# uDJV_board_1_v1_1.net
KiCad netlist of a schematic drawn in EAGLE
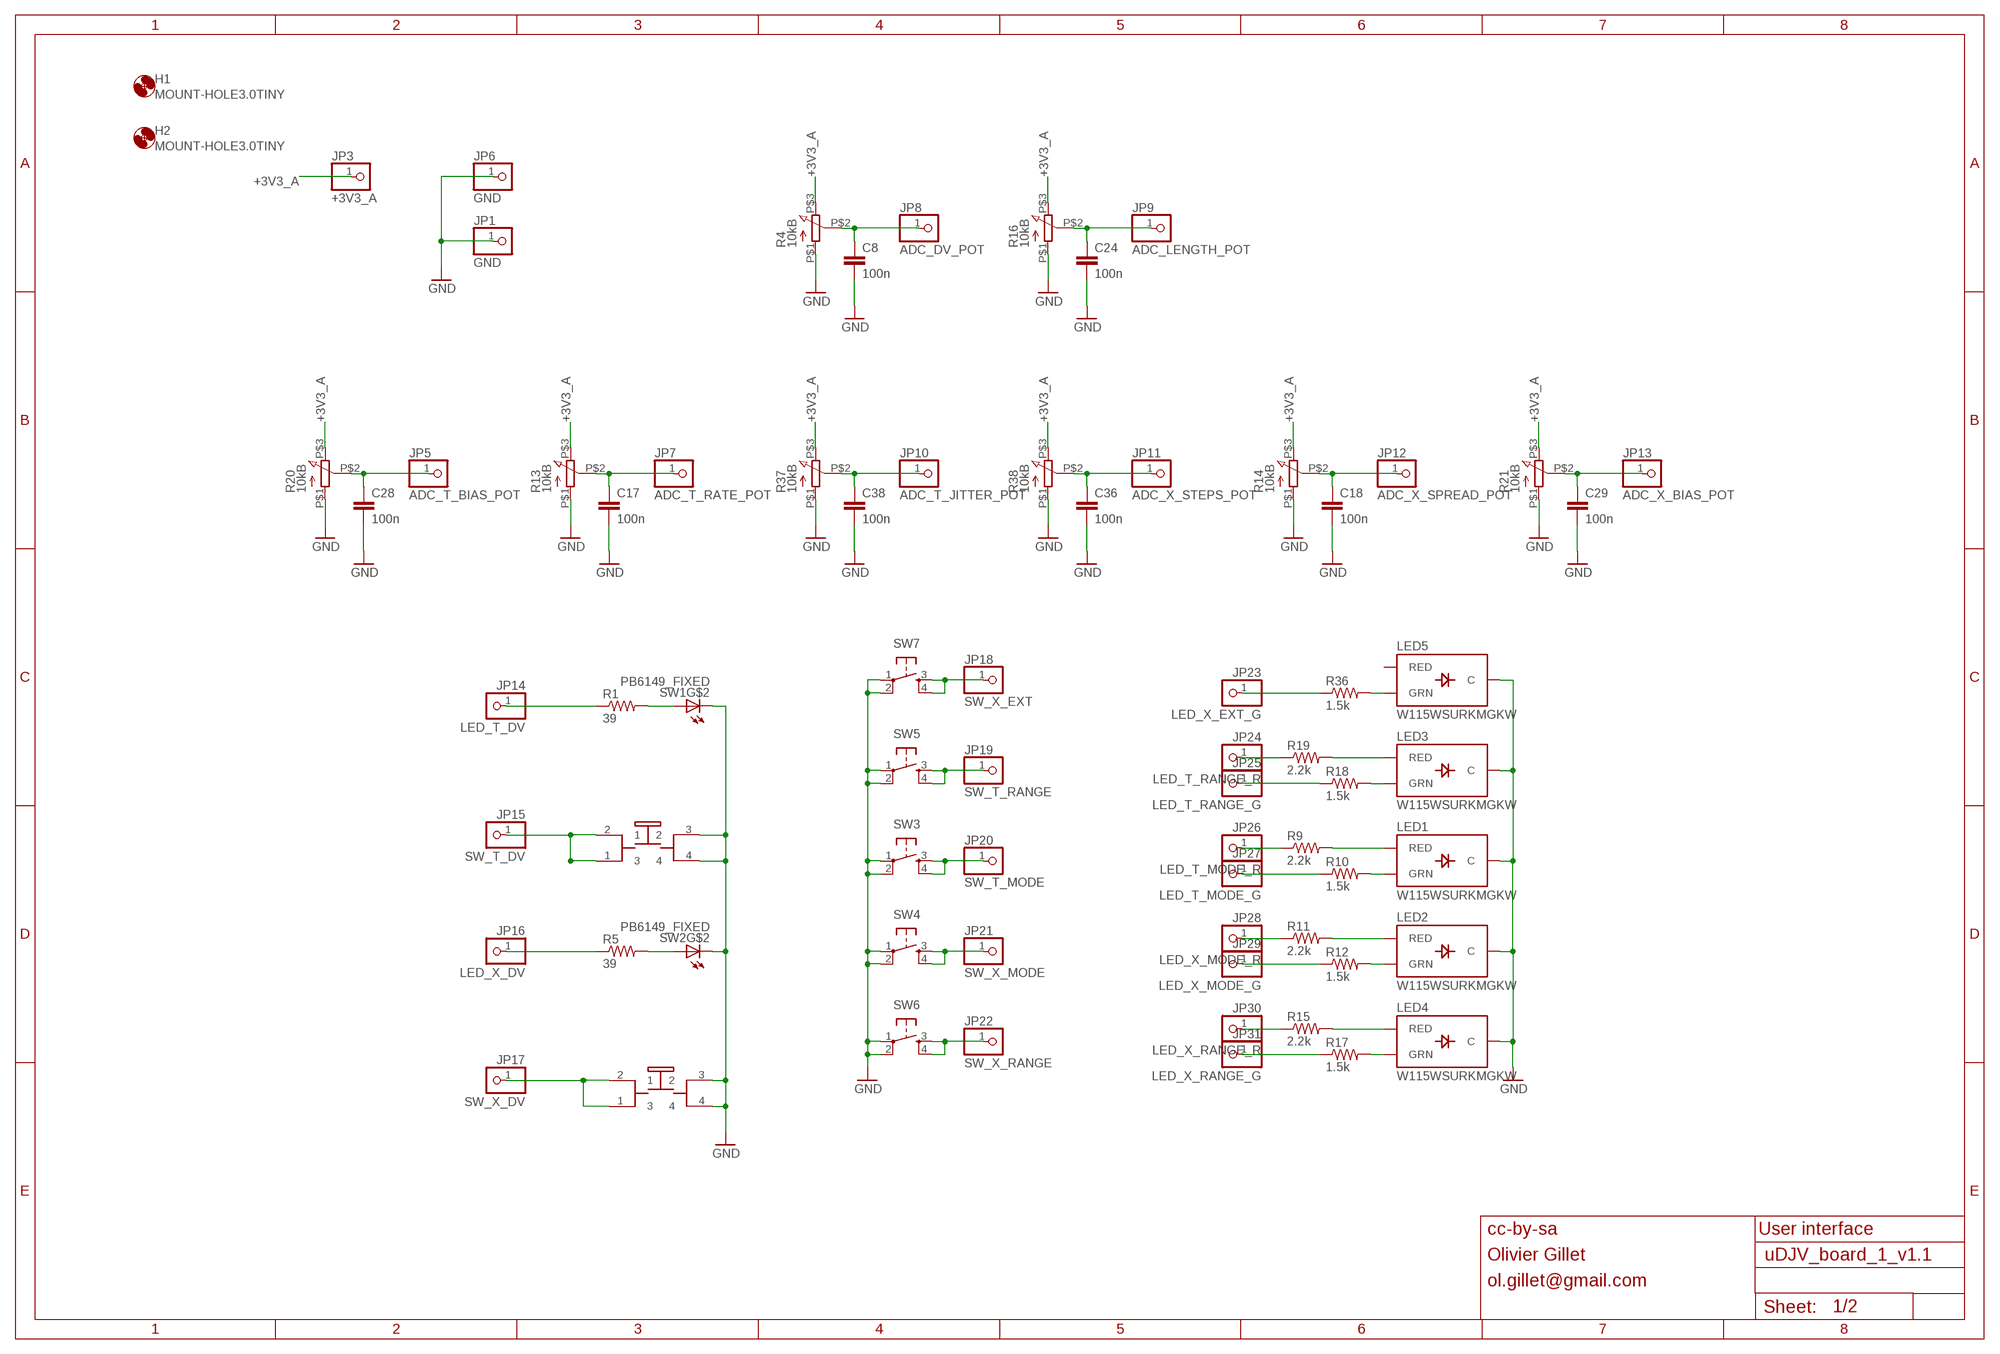
[diagram p0: schematic, sheet 1]
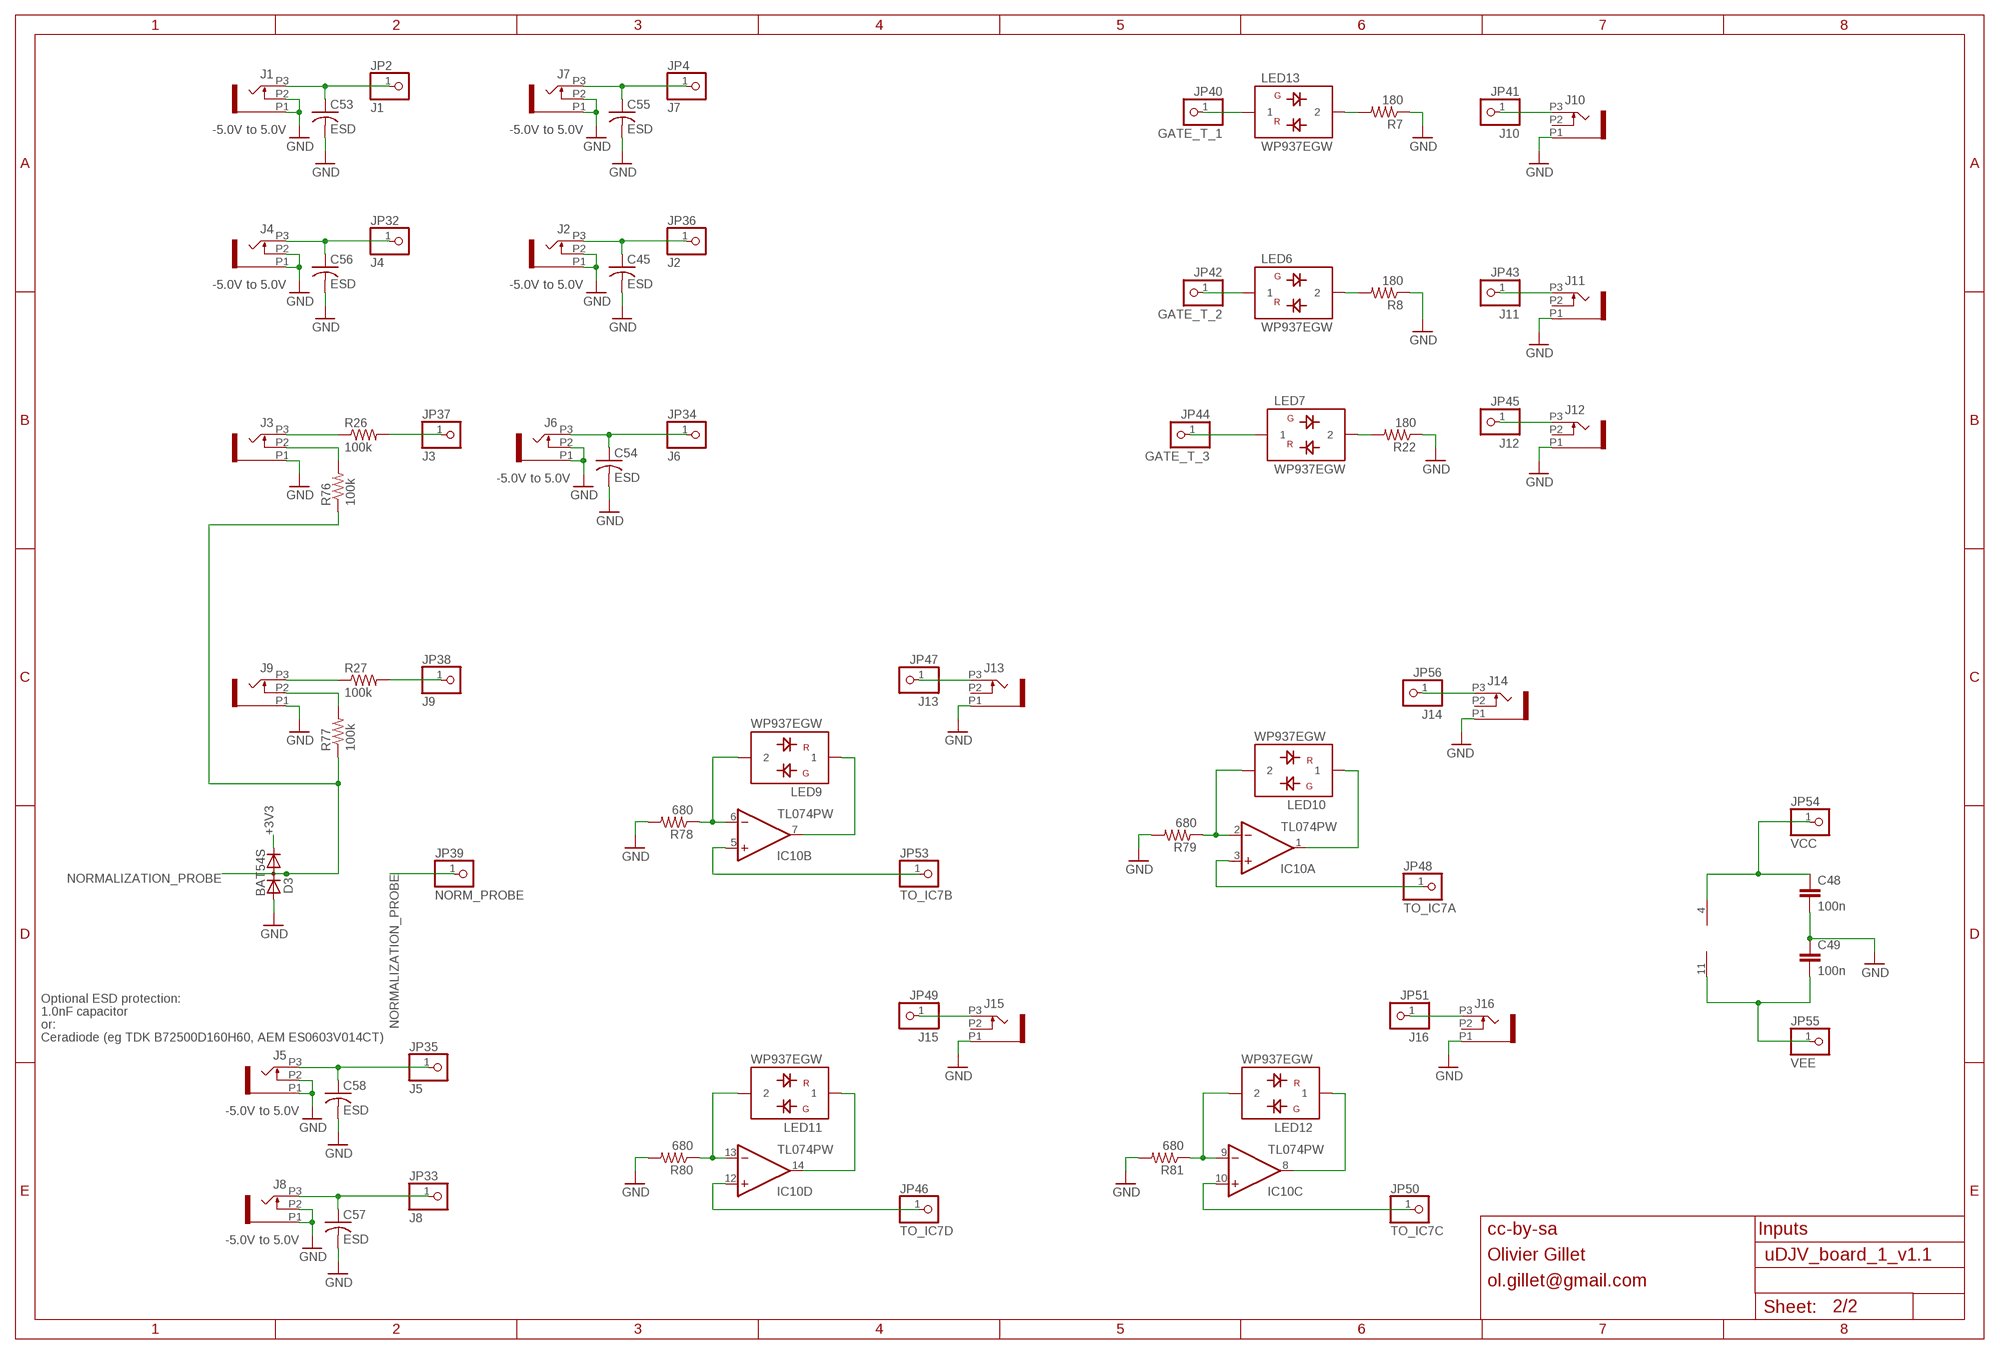
[diagram p1: schematic, sheet 2]

(export (version "E")
  (design (tool "Eeschema 10.0.6"))
  (components
    (comp (ref "C45")
      (value "ESD")
      (footprint "eagle-import:C0603")
      (libsource (lib "eagle-import") (part "C-USC0603"))
    )
    (comp (ref "C48")
      (value "100n")
      (footprint "eagle-import:PARTS_AMAN_RESISTOR_0603")
      (libsource (lib "eagle-import") (part "PARTS_AMAN_CAPACITOR"))
    )
    (comp (ref "C49")
      (value "100n")
      (footprint "eagle-import:PARTS_AMAN_RESISTOR_0603")
      (libsource (lib "eagle-import") (part "PARTS_AMAN_CAPACITOR"))
    )
    (comp (ref "C53")
      (value "ESD")
      (footprint "eagle-import:C0603")
      (libsource (lib "eagle-import") (part "C-USC0603"))
    )
    (comp (ref "C54")
      (value "ESD")
      (footprint "eagle-import:C0603")
      (libsource (lib "eagle-import") (part "C-USC0603"))
    )
    (comp (ref "C55")
      (value "ESD")
      (footprint "eagle-import:C0603")
      (libsource (lib "eagle-import") (part "C-USC0603"))
    )
    (comp (ref "C56")
      (value "ESD")
      (footprint "eagle-import:C0603")
      (libsource (lib "eagle-import") (part "C-USC0603"))
    )
    (comp (ref "C57")
      (value "ESD")
      (footprint "eagle-import:C0603")
      (libsource (lib "eagle-import") (part "C-USC0603"))
    )
    (comp (ref "C58")
      (value "ESD")
      (footprint "eagle-import:C0603")
      (libsource (lib "eagle-import") (part "C-USC0603"))
    )
    (comp (ref "D3")
      (value "BAT54S")
      (footprint "eagle-import:SOT23")
      (libsource (lib "eagle-import") (part "DIODE_2CACA-SOT23"))
    )
    (comp (ref "IC10")
      (value "TL074PW")
      (footprint "eagle-import:TSSOP14_065")
      (libsource (lib "eagle-import") (part "TL074PW"))
    )
    (comp (ref "J1")
      (value "PJ301_THONKICONN6")
      (footprint "eagle-import:WQP_PJ_301M6")
      (libsource (lib "eagle-import") (part "PJ301_THONKICONN6"))
    )
    (comp (ref "J2")
      (value "PJ301_THONKICONN6")
      (footprint "eagle-import:WQP_PJ_301M6")
      (libsource (lib "eagle-import") (part "PJ301_THONKICONN6"))
    )
    (comp (ref "J3")
      (value "PJ301_THONKICONN6")
      (footprint "eagle-import:WQP_PJ_301M6")
      (libsource (lib "eagle-import") (part "PJ301_THONKICONN6"))
    )
    (comp (ref "J4")
      (value "PJ301_THONKICONN6")
      (footprint "eagle-import:WQP_PJ_301M6")
      (libsource (lib "eagle-import") (part "PJ301_THONKICONN6"))
    )
    (comp (ref "J5")
      (value "PJ301_THONKICONN6")
      (footprint "eagle-import:WQP_PJ_301M6")
      (libsource (lib "eagle-import") (part "PJ301_THONKICONN6"))
    )
    (comp (ref "J6")
      (value "PJ301_THONKICONN6")
      (footprint "eagle-import:WQP_PJ_301M6")
      (libsource (lib "eagle-import") (part "PJ301_THONKICONN6"))
    )
    (comp (ref "J7")
      (value "PJ301_THONKICONN6")
      (footprint "eagle-import:WQP_PJ_301M6")
      (libsource (lib "eagle-import") (part "PJ301_THONKICONN6"))
    )
    (comp (ref "J8")
      (value "PJ301_THONKICONN6")
      (footprint "eagle-import:WQP_PJ_301M6")
      (libsource (lib "eagle-import") (part "PJ301_THONKICONN6"))
    )
    (comp (ref "J9")
      (value "PJ301_THONKICONN6")
      (footprint "eagle-import:WQP_PJ_301M6")
      (libsource (lib "eagle-import") (part "PJ301_THONKICONN6"))
    )
    (comp (ref "J10")
      (value "PJ301_THONKICONN6")
      (footprint "eagle-import:WQP_PJ_301M6")
      (libsource (lib "eagle-import") (part "PJ301_THONKICONN6"))
    )
    (comp (ref "J11")
      (value "PJ301_THONKICONN6")
      (footprint "eagle-import:WQP_PJ_301M6")
      (libsource (lib "eagle-import") (part "PJ301_THONKICONN6"))
    )
    (comp (ref "J12")
      (value "PJ301_THONKICONN6")
      (footprint "eagle-import:WQP_PJ_301M6")
      (libsource (lib "eagle-import") (part "PJ301_THONKICONN6"))
    )
    (comp (ref "J13")
      (value "PJ301_THONKICONN6")
      (footprint "eagle-import:WQP_PJ_301M6")
      (libsource (lib "eagle-import") (part "PJ301_THONKICONN6"))
    )
    (comp (ref "J14")
      (value "PJ301_THONKICONN6")
      (footprint "eagle-import:WQP_PJ_301M6")
      (libsource (lib "eagle-import") (part "PJ301_THONKICONN6"))
    )
    (comp (ref "J15")
      (value "PJ301_THONKICONN6")
      (footprint "eagle-import:WQP_PJ_301M6")
      (libsource (lib "eagle-import") (part "PJ301_THONKICONN6"))
    )
    (comp (ref "J16")
      (value "PJ301_THONKICONN6")
      (footprint "eagle-import:WQP_PJ_301M6")
      (libsource (lib "eagle-import") (part "PJ301_THONKICONN6"))
    )
    (comp (ref "JP2")
      (value "J1")
      (footprint "eagle-import:PARTS_AMAN_1X01")
      (libsource (lib "eagle-import") (part "PARTS_AMAN_PINHD-1X1"))
    )
    (comp (ref "JP4")
      (value "J7")
      (footprint "eagle-import:PARTS_AMAN_1X01")
      (libsource (lib "eagle-import") (part "PARTS_AMAN_PINHD-1X1"))
    )
    (comp (ref "JP32")
      (value "J4")
      (footprint "eagle-import:PARTS_AMAN_1X01")
      (libsource (lib "eagle-import") (part "PARTS_AMAN_PINHD-1X1"))
    )
    (comp (ref "JP33")
      (value "J8")
      (footprint "eagle-import:PARTS_AMAN_1X01")
      (libsource (lib "eagle-import") (part "PARTS_AMAN_PINHD-1X1"))
    )
    (comp (ref "JP34")
      (value "J6")
      (footprint "eagle-import:PARTS_AMAN_1X01")
      (libsource (lib "eagle-import") (part "PARTS_AMAN_PINHD-1X1"))
    )
    (comp (ref "JP35")
      (value "J5")
      (footprint "eagle-import:PARTS_AMAN_1X01")
      (libsource (lib "eagle-import") (part "PARTS_AMAN_PINHD-1X1"))
    )
    (comp (ref "JP36")
      (value "J2")
      (footprint "eagle-import:PARTS_AMAN_1X01")
      (libsource (lib "eagle-import") (part "PARTS_AMAN_PINHD-1X1"))
    )
    (comp (ref "JP37")
      (value "J3")
      (footprint "eagle-import:PARTS_AMAN_1X01")
      (libsource (lib "eagle-import") (part "PARTS_AMAN_PINHD-1X1"))
    )
    (comp (ref "JP38")
      (value "J9")
      (footprint "eagle-import:PARTS_AMAN_1X01")
      (libsource (lib "eagle-import") (part "PARTS_AMAN_PINHD-1X1"))
    )
    (comp (ref "JP39")
      (value "NORM_PROBE")
      (footprint "eagle-import:PARTS_AMAN_1X01")
      (libsource (lib "eagle-import") (part "PARTS_AMAN_PINHD-1X1"))
    )
    (comp (ref "JP40")
      (value "GATE_T_1")
      (footprint "eagle-import:PARTS_AMAN_1X01")
      (libsource (lib "eagle-import") (part "PARTS_AMAN_PINHD-1X1"))
    )
    (comp (ref "JP41")
      (value "J10")
      (footprint "eagle-import:PARTS_AMAN_1X01")
      (libsource (lib "eagle-import") (part "PARTS_AMAN_PINHD-1X1"))
    )
    (comp (ref "JP42")
      (value "GATE_T_2")
      (footprint "eagle-import:PARTS_AMAN_1X01")
      (libsource (lib "eagle-import") (part "PARTS_AMAN_PINHD-1X1"))
    )
    (comp (ref "JP43")
      (value "J11")
      (footprint "eagle-import:PARTS_AMAN_1X01")
      (libsource (lib "eagle-import") (part "PARTS_AMAN_PINHD-1X1"))
    )
    (comp (ref "JP44")
      (value "GATE_T_3")
      (footprint "eagle-import:PARTS_AMAN_1X01")
      (libsource (lib "eagle-import") (part "PARTS_AMAN_PINHD-1X1"))
    )
    (comp (ref "JP45")
      (value "J12")
      (footprint "eagle-import:PARTS_AMAN_1X01")
      (libsource (lib "eagle-import") (part "PARTS_AMAN_PINHD-1X1"))
    )
    (comp (ref "JP46")
      (value "TO_IC7D")
      (footprint "eagle-import:PARTS_AMAN_1X01")
      (libsource (lib "eagle-import") (part "PARTS_AMAN_PINHD-1X1"))
    )
    (comp (ref "JP47")
      (value "J13")
      (footprint "eagle-import:PARTS_AMAN_1X01")
      (libsource (lib "eagle-import") (part "PARTS_AMAN_PINHD-1X1"))
    )
    (comp (ref "JP48")
      (value "TO_IC7A")
      (footprint "eagle-import:PARTS_AMAN_1X01")
      (libsource (lib "eagle-import") (part "PARTS_AMAN_PINHD-1X1"))
    )
    (comp (ref "JP49")
      (value "J15")
      (footprint "eagle-import:PARTS_AMAN_1X01")
      (libsource (lib "eagle-import") (part "PARTS_AMAN_PINHD-1X1"))
    )
    (comp (ref "JP50")
      (value "TO_IC7C")
      (footprint "eagle-import:PARTS_AMAN_1X01")
      (libsource (lib "eagle-import") (part "PARTS_AMAN_PINHD-1X1"))
    )
    (comp (ref "JP51")
      (value "J16")
      (footprint "eagle-import:PARTS_AMAN_1X01")
      (libsource (lib "eagle-import") (part "PARTS_AMAN_PINHD-1X1"))
    )
    (comp (ref "JP53")
      (value "TO_IC7B")
      (footprint "eagle-import:PARTS_AMAN_1X01")
      (libsource (lib "eagle-import") (part "PARTS_AMAN_PINHD-1X1"))
    )
    (comp (ref "JP54")
      (value "VCC")
      (footprint "eagle-import:PARTS_AMAN_1X01")
      (libsource (lib "eagle-import") (part "PARTS_AMAN_PINHD-1X1"))
    )
    (comp (ref "JP55")
      (value "VEE")
      (footprint "eagle-import:PARTS_AMAN_1X01")
      (libsource (lib "eagle-import") (part "PARTS_AMAN_PINHD-1X1"))
    )
    (comp (ref "JP56")
      (value "J14")
      (footprint "eagle-import:PARTS_AMAN_1X01")
      (libsource (lib "eagle-import") (part "PARTS_AMAN_PINHD-1X1"))
    )
    (comp (ref "LED6")
      (value "WP937EGW")
      (footprint "eagle-import:LED3MM")
      (libsource (lib "eagle-import") (part "LED-BICOLOR-SHARED-THROUGHHOLE"))
    )
    (comp (ref "LED7")
      (value "WP937EGW")
      (footprint "eagle-import:LED3MM")
      (libsource (lib "eagle-import") (part "LED-BICOLOR-SHARED-THROUGHHOLE"))
    )
    (comp (ref "LED9")
      (value "WP937EGW")
      (footprint "eagle-import:LED3MM")
      (libsource (lib "eagle-import") (part "LED-BICOLOR-SHARED-THROUGHHOLE"))
    )
    (comp (ref "LED10")
      (value "WP937EGW")
      (footprint "eagle-import:LED3MM")
      (libsource (lib "eagle-import") (part "LED-BICOLOR-SHARED-THROUGHHOLE"))
    )
    (comp (ref "LED11")
      (value "WP937EGW")
      (footprint "eagle-import:LED3MM")
      (libsource (lib "eagle-import") (part "LED-BICOLOR-SHARED-THROUGHHOLE"))
    )
    (comp (ref "LED12")
      (value "WP937EGW")
      (footprint "eagle-import:LED3MM")
      (libsource (lib "eagle-import") (part "LED-BICOLOR-SHARED-THROUGHHOLE"))
    )
    (comp (ref "LED13")
      (value "WP937EGW")
      (footprint "eagle-import:LED3MM")
      (libsource (lib "eagle-import") (part "LED-BICOLOR-SHARED-THROUGHHOLE"))
    )
    (comp (ref "R7")
      (value "180")
      (footprint "eagle-import:PARTS_AMAN_RESISTOR_0603")
      (libsource (lib "eagle-import") (part "PARTS_AMAN_RESISTOR"))
    )
    (comp (ref "R8")
      (value "180")
      (footprint "eagle-import:PARTS_AMAN_RESISTOR_0603")
      (libsource (lib "eagle-import") (part "PARTS_AMAN_RESISTOR"))
    )
    (comp (ref "R22")
      (value "180")
      (footprint "eagle-import:PARTS_AMAN_RESISTOR_0603")
      (libsource (lib "eagle-import") (part "PARTS_AMAN_RESISTOR"))
    )
    (comp (ref "R26")
      (value "100k")
      (footprint "eagle-import:PARTS_AMAN_RESISTOR_0603")
      (libsource (lib "eagle-import") (part "PARTS_AMAN_RESISTOR"))
    )
    (comp (ref "R27")
      (value "100k")
      (footprint "eagle-import:PARTS_AMAN_RESISTOR_0603")
      (libsource (lib "eagle-import") (part "PARTS_AMAN_RESISTOR"))
    )
    (comp (ref "R76")
      (value "100k")
      (footprint "eagle-import:PARTS_AMAN_RESISTOR_0603")
      (libsource (lib "eagle-import") (part "PARTS_AMAN_RESISTOR"))
    )
    (comp (ref "R77")
      (value "100k")
      (footprint "eagle-import:PARTS_AMAN_RESISTOR_0603")
      (libsource (lib "eagle-import") (part "PARTS_AMAN_RESISTOR"))
    )
    (comp (ref "R78")
      (value "680")
      (footprint "eagle-import:PARTS_AMAN_RESISTOR_0603")
      (libsource (lib "eagle-import") (part "PARTS_AMAN_RESISTOR"))
    )
    (comp (ref "R79")
      (value "680")
      (footprint "eagle-import:PARTS_AMAN_RESISTOR_0603")
      (libsource (lib "eagle-import") (part "PARTS_AMAN_RESISTOR"))
    )
    (comp (ref "R80")
      (value "680")
      (footprint "eagle-import:PARTS_AMAN_RESISTOR_0603")
      (libsource (lib "eagle-import") (part "PARTS_AMAN_RESISTOR"))
    )
    (comp (ref "R81")
      (value "680")
      (footprint "eagle-import:PARTS_AMAN_RESISTOR_0603")
      (libsource (lib "eagle-import") (part "PARTS_AMAN_RESISTOR"))
    )
    (comp (ref "C8")
      (value "100n")
      (footprint "eagle-import:PARTS_AMAN_RESISTOR_0603")
      (libsource (lib "eagle-import") (part "PARTS_AMAN_CAPACITOR"))
    )
    (comp (ref "C17")
      (value "100n")
      (footprint "eagle-import:PARTS_AMAN_RESISTOR_0603")
      (libsource (lib "eagle-import") (part "PARTS_AMAN_CAPACITOR"))
    )
    (comp (ref "C18")
      (value "100n")
      (footprint "eagle-import:PARTS_AMAN_RESISTOR_0603")
      (libsource (lib "eagle-import") (part "PARTS_AMAN_CAPACITOR"))
    )
    (comp (ref "C24")
      (value "100n")
      (footprint "eagle-import:PARTS_AMAN_RESISTOR_0603")
      (libsource (lib "eagle-import") (part "PARTS_AMAN_CAPACITOR"))
    )
    (comp (ref "C28")
      (value "100n")
      (footprint "eagle-import:PARTS_AMAN_RESISTOR_0603")
      (libsource (lib "eagle-import") (part "PARTS_AMAN_CAPACITOR"))
    )
    (comp (ref "C29")
      (value "100n")
      (footprint "eagle-import:PARTS_AMAN_RESISTOR_0603")
      (libsource (lib "eagle-import") (part "PARTS_AMAN_CAPACITOR"))
    )
    (comp (ref "C36")
      (value "100n")
      (footprint "eagle-import:PARTS_AMAN_RESISTOR_0603")
      (libsource (lib "eagle-import") (part "PARTS_AMAN_CAPACITOR"))
    )
    (comp (ref "C38")
      (value "100n")
      (footprint "eagle-import:PARTS_AMAN_RESISTOR_0603")
      (libsource (lib "eagle-import") (part "PARTS_AMAN_CAPACITOR"))
    )
    (comp (ref "H1")
      (value "MOUNT-HOLE3.0TINY")
      (footprint "eagle-import:3,0TINY")
      (libsource (lib "eagle-import") (part "MOUNT-HOLE3.0TINY"))
    )
    (comp (ref "H2")
      (value "MOUNT-HOLE3.0TINY")
      (footprint "eagle-import:3,0TINY")
      (libsource (lib "eagle-import") (part "MOUNT-HOLE3.0TINY"))
    )
    (comp (ref "JP1")
      (value "GND")
      (footprint "eagle-import:PARTS_AMAN_1X01")
      (libsource (lib "eagle-import") (part "PARTS_AMAN_PINHD-1X1"))
    )
    (comp (ref "JP3")
      (value "+3V3_A")
      (footprint "eagle-import:PARTS_AMAN_1X01")
      (libsource (lib "eagle-import") (part "PARTS_AMAN_PINHD-1X1"))
    )
    (comp (ref "JP5")
      (value "ADC_T_BIAS_POT")
      (footprint "eagle-import:PARTS_AMAN_1X01")
      (libsource (lib "eagle-import") (part "PARTS_AMAN_PINHD-1X1"))
    )
    (comp (ref "JP6")
      (value "GND")
      (footprint "eagle-import:PARTS_AMAN_1X01")
      (libsource (lib "eagle-import") (part "PARTS_AMAN_PINHD-1X1"))
    )
    (comp (ref "JP7")
      (value "ADC_T_RATE_POT")
      (footprint "eagle-import:PARTS_AMAN_1X01")
      (libsource (lib "eagle-import") (part "PARTS_AMAN_PINHD-1X1"))
    )
    (comp (ref "JP8")
      (value "ADC_DV_POT")
      (footprint "eagle-import:PARTS_AMAN_1X01")
      (libsource (lib "eagle-import") (part "PARTS_AMAN_PINHD-1X1"))
    )
    (comp (ref "JP9")
      (value "ADC_LENGTH_POT")
      (footprint "eagle-import:PARTS_AMAN_1X01")
      (libsource (lib "eagle-import") (part "PARTS_AMAN_PINHD-1X1"))
    )
    (comp (ref "JP10")
      (value "ADC_T_JITTER_POT")
      (footprint "eagle-import:PARTS_AMAN_1X01")
      (libsource (lib "eagle-import") (part "PARTS_AMAN_PINHD-1X1"))
    )
    (comp (ref "JP11")
      (value "ADC_X_STEPS_POT")
      (footprint "eagle-import:PARTS_AMAN_1X01")
      (libsource (lib "eagle-import") (part "PARTS_AMAN_PINHD-1X1"))
    )
    (comp (ref "JP12")
      (value "ADC_X_SPREAD_POT")
      (footprint "eagle-import:PARTS_AMAN_1X01")
      (libsource (lib "eagle-import") (part "PARTS_AMAN_PINHD-1X1"))
    )
    (comp (ref "JP13")
      (value "ADC_X_BIAS_POT")
      (footprint "eagle-import:PARTS_AMAN_1X01")
      (libsource (lib "eagle-import") (part "PARTS_AMAN_PINHD-1X1"))
    )
    (comp (ref "JP14")
      (value "LED_T_DV")
      (footprint "eagle-import:PARTS_AMAN_1X01")
      (libsource (lib "eagle-import") (part "PARTS_AMAN_PINHD-1X1"))
    )
    (comp (ref "JP15")
      (value "SW_T_DV")
      (footprint "eagle-import:PARTS_AMAN_1X01")
      (libsource (lib "eagle-import") (part "PARTS_AMAN_PINHD-1X1"))
    )
    (comp (ref "JP16")
      (value "LED_X_DV")
      (footprint "eagle-import:PARTS_AMAN_1X01")
      (libsource (lib "eagle-import") (part "PARTS_AMAN_PINHD-1X1"))
    )
    (comp (ref "JP17")
      (value "SW_X_DV")
      (footprint "eagle-import:PARTS_AMAN_1X01")
      (libsource (lib "eagle-import") (part "PARTS_AMAN_PINHD-1X1"))
    )
    (comp (ref "JP18")
      (value "SW_X_EXT")
      (footprint "eagle-import:PARTS_AMAN_1X01")
      (libsource (lib "eagle-import") (part "PARTS_AMAN_PINHD-1X1"))
    )
    (comp (ref "JP19")
      (value "SW_T_RANGE")
      (footprint "eagle-import:PARTS_AMAN_1X01")
      (libsource (lib "eagle-import") (part "PARTS_AMAN_PINHD-1X1"))
    )
    (comp (ref "JP20")
      (value "SW_T_MODE")
      (footprint "eagle-import:PARTS_AMAN_1X01")
      (libsource (lib "eagle-import") (part "PARTS_AMAN_PINHD-1X1"))
    )
    (comp (ref "JP21")
      (value "SW_X_MODE")
      (footprint "eagle-import:PARTS_AMAN_1X01")
      (libsource (lib "eagle-import") (part "PARTS_AMAN_PINHD-1X1"))
    )
    (comp (ref "JP22")
      (value "SW_X_RANGE")
      (footprint "eagle-import:PARTS_AMAN_1X01")
      (libsource (lib "eagle-import") (part "PARTS_AMAN_PINHD-1X1"))
    )
    (comp (ref "JP23")
      (value "LED_X_EXT_G")
      (footprint "eagle-import:PARTS_AMAN_1X01")
      (libsource (lib "eagle-import") (part "PARTS_AMAN_PINHD-1X1"))
    )
    (comp (ref "JP24")
      (value "LED_T_RANGE_R")
      (footprint "eagle-import:PARTS_AMAN_1X01")
      (libsource (lib "eagle-import") (part "PARTS_AMAN_PINHD-1X1"))
    )
    (comp (ref "JP25")
      (value "LED_T_RANGE_G")
      (footprint "eagle-import:PARTS_AMAN_1X01")
      (libsource (lib "eagle-import") (part "PARTS_AMAN_PINHD-1X1"))
    )
    (comp (ref "JP26")
      (value "LED_T_MODE_R")
      (footprint "eagle-import:PARTS_AMAN_1X01")
      (libsource (lib "eagle-import") (part "PARTS_AMAN_PINHD-1X1"))
    )
    (comp (ref "JP27")
      (value "LED_T_MODE_G")
      (footprint "eagle-import:PARTS_AMAN_1X01")
      (libsource (lib "eagle-import") (part "PARTS_AMAN_PINHD-1X1"))
    )
    (comp (ref "JP28")
      (value "LED_X_MODE_R")
      (footprint "eagle-import:PARTS_AMAN_1X01")
      (libsource (lib "eagle-import") (part "PARTS_AMAN_PINHD-1X1"))
    )
    (comp (ref "JP29")
      (value "LED_X_MODE_G")
      (footprint "eagle-import:PARTS_AMAN_1X01")
      (libsource (lib "eagle-import") (part "PARTS_AMAN_PINHD-1X1"))
    )
    (comp (ref "JP30")
      (value "LED_X_RANGE_R")
      (footprint "eagle-import:PARTS_AMAN_1X01")
      (libsource (lib "eagle-import") (part "PARTS_AMAN_PINHD-1X1"))
    )
    (comp (ref "JP31")
      (value "LED_X_RANGE_G")
      (footprint "eagle-import:PARTS_AMAN_1X01")
      (libsource (lib "eagle-import") (part "PARTS_AMAN_PINHD-1X1"))
    )
    (comp (ref "LED1")
      (value "W115WSURKMGKW")
      (footprint "eagle-import:LED-BICOLOR-THROUGHHOLE-2.54")
      (libsource (lib "eagle-import") (part "LED-BICOLOR-THROUGHHOLE2.54"))
    )
    (comp (ref "LED2")
      (value "W115WSURKMGKW")
      (footprint "eagle-import:LED-BICOLOR-THROUGHHOLE-2.54")
      (libsource (lib "eagle-import") (part "LED-BICOLOR-THROUGHHOLE2.54"))
    )
    (comp (ref "LED3")
      (value "W115WSURKMGKW")
      (footprint "eagle-import:LED-BICOLOR-THROUGHHOLE-2.54")
      (libsource (lib "eagle-import") (part "LED-BICOLOR-THROUGHHOLE2.54"))
    )
    (comp (ref "LED4")
      (value "W115WSURKMGKW")
      (footprint "eagle-import:LED-BICOLOR-THROUGHHOLE-2.54")
      (libsource (lib "eagle-import") (part "LED-BICOLOR-THROUGHHOLE2.54"))
    )
    (comp (ref "LED5")
      (value "W115WSURKMGKW")
      (footprint "eagle-import:LED-BICOLOR-THROUGHHOLE-2.54")
      (libsource (lib "eagle-import") (part "LED-BICOLOR-THROUGHHOLE2.54"))
    )
    (comp (ref "R1")
      (value "39")
      (footprint "eagle-import:PARTS_AMAN_RESISTOR_0603")
      (libsource (lib "eagle-import") (part "PARTS_AMAN_RESISTOR"))
    )
    (comp (ref "R4")
      (value "10kB")
      (footprint "eagle-import:Q-POT2")
      (libsource (lib "eagle-import") (part "Q-POT2"))
    )
    (comp (ref "R5")
      (value "39")
      (footprint "eagle-import:PARTS_AMAN_RESISTOR_0603")
      (libsource (lib "eagle-import") (part "PARTS_AMAN_RESISTOR"))
    )
    (comp (ref "R9")
      (value "2.2k")
      (footprint "eagle-import:PARTS_AMAN_RESISTOR_0603")
      (libsource (lib "eagle-import") (part "PARTS_AMAN_RESISTOR"))
    )
    (comp (ref "R10")
      (value "1.5k")
      (footprint "eagle-import:PARTS_AMAN_RESISTOR_0603")
      (libsource (lib "eagle-import") (part "PARTS_AMAN_RESISTOR"))
    )
    (comp (ref "R11")
      (value "2.2k")
      (footprint "eagle-import:PARTS_AMAN_RESISTOR_0603")
      (libsource (lib "eagle-import") (part "PARTS_AMAN_RESISTOR"))
    )
    (comp (ref "R12")
      (value "1.5k")
      (footprint "eagle-import:PARTS_AMAN_RESISTOR_0603")
      (libsource (lib "eagle-import") (part "PARTS_AMAN_RESISTOR"))
    )
    (comp (ref "R13")
      (value "10kB")
      (footprint "eagle-import:Q-POT2")
      (libsource (lib "eagle-import") (part "Q-POT2"))
    )
    (comp (ref "R14")
      (value "10kB")
      (footprint "eagle-import:Q-POT2")
      (libsource (lib "eagle-import") (part "Q-POT2"))
    )
    (comp (ref "R15")
      (value "2.2k")
      (footprint "eagle-import:PARTS_AMAN_RESISTOR_0603")
      (libsource (lib "eagle-import") (part "PARTS_AMAN_RESISTOR"))
    )
    (comp (ref "R16")
      (value "10kB")
      (footprint "eagle-import:Q-POT2")
      (libsource (lib "eagle-import") (part "Q-POT2"))
    )
    (comp (ref "R17")
      (value "1.5k")
      (footprint "eagle-import:PARTS_AMAN_RESISTOR_0603")
      (libsource (lib "eagle-import") (part "PARTS_AMAN_RESISTOR"))
    )
    (comp (ref "R18")
      (value "1.5k")
      (footprint "eagle-import:PARTS_AMAN_RESISTOR_0603")
      (libsource (lib "eagle-import") (part "PARTS_AMAN_RESISTOR"))
    )
    (comp (ref "R19")
      (value "2.2k")
      (footprint "eagle-import:PARTS_AMAN_RESISTOR_0603")
      (libsource (lib "eagle-import") (part "PARTS_AMAN_RESISTOR"))
    )
    (comp (ref "R20")
      (value "10kB")
      (footprint "eagle-import:Q-POT2")
      (libsource (lib "eagle-import") (part "Q-POT2"))
    )
    (comp (ref "R21")
      (value "10kB")
      (footprint "eagle-import:Q-POT2")
      (libsource (lib "eagle-import") (part "Q-POT2"))
    )
    (comp (ref "R36")
      (value "1.5k")
      (footprint "eagle-import:PARTS_AMAN_RESISTOR_0603")
      (libsource (lib "eagle-import") (part "PARTS_AMAN_RESISTOR"))
    )
    (comp (ref "R37")
      (value "10kB")
      (footprint "eagle-import:Q-POT2")
      (libsource (lib "eagle-import") (part "Q-POT2"))
    )
    (comp (ref "R38")
      (value "10kB")
      (footprint "eagle-import:Q-POT2")
      (libsource (lib "eagle-import") (part "Q-POT2"))
    )
    (comp (ref "SW1")
      (value "PB6149_FIXED")
      (footprint "eagle-import:PB6149L")
      (libsource (lib "eagle-import") (part "PB6149_FIXED"))
    )
    (comp (ref "SW2")
      (value "PB6149_FIXED")
      (footprint "eagle-import:PB6149L")
      (libsource (lib "eagle-import") (part "PB6149_FIXED"))
    )
    (comp (ref "SW3")
      (value "TAC_SWITCHPTH")
      (footprint "eagle-import:TACTILE-PTH")
      (libsource (lib "eagle-import") (part "TAC_SWITCHPTH"))
    )
    (comp (ref "SW4")
      (value "TAC_SWITCHPTH")
      (footprint "eagle-import:TACTILE-PTH")
      (libsource (lib "eagle-import") (part "TAC_SWITCHPTH"))
    )
    (comp (ref "SW5")
      (value "TAC_SWITCHPTH")
      (footprint "eagle-import:TACTILE-PTH")
      (libsource (lib "eagle-import") (part "TAC_SWITCHPTH"))
    )
    (comp (ref "SW6")
      (value "TAC_SWITCHPTH")
      (footprint "eagle-import:TACTILE-PTH")
      (libsource (lib "eagle-import") (part "TAC_SWITCHPTH"))
    )
    (comp (ref "SW7")
      (value "TAC_SWITCHPTH")
      (footprint "eagle-import:TACTILE-PTH")
      (libsource (lib "eagle-import") (part "TAC_SWITCHPTH"))
    )
  )
  (nets
    (net (code "1") (name "+3V3") (class "Default")
      (node (ref "D3") (pin "2") (pinfunction "C_2") (pintype "passive"))
    )
    (net (code "2") (name "+3V3_A") (class "Default")
      (node (ref "JP3") (pin "1") (pinfunction "1_1") (pintype "passive"))
      (node (ref "R13") (pin "P$3") (pinfunction "3_P$3") (pintype "passive"))
      (node (ref "R14") (pin "P$3") (pinfunction "3_P$3") (pintype "passive"))
      (node (ref "R16") (pin "P$3") (pinfunction "3_P$3") (pintype "passive"))
      (node (ref "R20") (pin "P$3") (pinfunction "3_P$3") (pintype "passive"))
      (node (ref "R21") (pin "P$3") (pinfunction "3_P$3") (pintype "passive"))
      (node (ref "R37") (pin "P$3") (pinfunction "3_P$3") (pintype "passive"))
      (node (ref "R38") (pin "P$3") (pinfunction "3_P$3") (pintype "passive"))
      (node (ref "R4") (pin "P$3") (pinfunction "3_P$3") (pintype "passive"))
    )
    (net (code "3") (name "GND") (class "Default")
      (node (ref "C17") (pin "2") (pinfunction "2_2") (pintype "passive"))
      (node (ref "C18") (pin "2") (pinfunction "2_2") (pintype "passive"))
      (node (ref "C24") (pin "2") (pinfunction "2_2") (pintype "passive"))
      (node (ref "C28") (pin "2") (pinfunction "2_2") (pintype "passive"))
      (node (ref "C29") (pin "2") (pinfunction "2_2") (pintype "passive"))
      (node (ref "C36") (pin "2") (pinfunction "2_2") (pintype "passive"))
      (node (ref "C38") (pin "2") (pinfunction "2_2") (pintype "passive"))
      (node (ref "C45") (pin "2") (pinfunction "2_2") (pintype "passive"))
      (node (ref "C48") (pin "2") (pinfunction "2_2") (pintype "passive"))
      (node (ref "C49") (pin "1") (pinfunction "1_1") (pintype "passive"))
      (node (ref "C53") (pin "2") (pinfunction "2_2") (pintype "passive"))
      (node (ref "C54") (pin "2") (pinfunction "2_2") (pintype "passive"))
      (node (ref "C55") (pin "2") (pinfunction "2_2") (pintype "passive"))
      (node (ref "C56") (pin "2") (pinfunction "2_2") (pintype "passive"))
      (node (ref "C57") (pin "2") (pinfunction "2_2") (pintype "passive"))
      (node (ref "C58") (pin "2") (pinfunction "2_2") (pintype "passive"))
      (node (ref "C8") (pin "2") (pinfunction "2_2") (pintype "passive"))
      (node (ref "D3") (pin "1") (pinfunction "A_1") (pintype "passive"))
      (node (ref "J1") (pin "P1") (pinfunction "1_P1") (pintype "passive"))
      (node (ref "J1") (pin "P2") (pinfunction "2_P2") (pintype "passive"))
      (node (ref "J10") (pin "P1") (pinfunction "1_P1") (pintype "passive"))
      (node (ref "J11") (pin "P1") (pinfunction "1_P1") (pintype "passive"))
      (node (ref "J12") (pin "P1") (pinfunction "1_P1") (pintype "passive"))
      (node (ref "J13") (pin "P1") (pinfunction "1_P1") (pintype "passive"))
      (node (ref "J14") (pin "P1") (pinfunction "1_P1") (pintype "passive"))
      (node (ref "J15") (pin "P1") (pinfunction "1_P1") (pintype "passive"))
      (node (ref "J16") (pin "P1") (pinfunction "1_P1") (pintype "passive"))
      (node (ref "J2") (pin "P1") (pinfunction "1_P1") (pintype "passive"))
      (node (ref "J2") (pin "P2") (pinfunction "2_P2") (pintype "passive"))
      (node (ref "J3") (pin "P1") (pinfunction "1_P1") (pintype "passive"))
      (node (ref "J4") (pin "P1") (pinfunction "1_P1") (pintype "passive"))
      (node (ref "J4") (pin "P2") (pinfunction "2_P2") (pintype "passive"))
      (node (ref "J5") (pin "P1") (pinfunction "1_P1") (pintype "passive"))
      (node (ref "J5") (pin "P2") (pinfunction "2_P2") (pintype "passive"))
      (node (ref "J6") (pin "P1") (pinfunction "1_P1") (pintype "passive"))
      (node (ref "J6") (pin "P2") (pinfunction "2_P2") (pintype "passive"))
      (node (ref "J7") (pin "P1") (pinfunction "1_P1") (pintype "passive"))
      (node (ref "J7") (pin "P2") (pinfunction "2_P2") (pintype "passive"))
      (node (ref "J8") (pin "P1") (pinfunction "1_P1") (pintype "passive"))
      (node (ref "J8") (pin "P2") (pinfunction "2_P2") (pintype "passive"))
      (node (ref "J9") (pin "P1") (pinfunction "1_P1") (pintype "passive"))
      (node (ref "JP1") (pin "1") (pinfunction "1_1") (pintype "passive"))
      (node (ref "JP6") (pin "1") (pinfunction "1_1") (pintype "passive"))
      (node (ref "LED1") (pin "2") (pinfunction "C_2") (pintype "bidirectional"))
      (node (ref "LED2") (pin "2") (pinfunction "C_2") (pintype "bidirectional"))
      (node (ref "LED3") (pin "2") (pinfunction "C_2") (pintype "bidirectional"))
      (node (ref "LED4") (pin "2") (pinfunction "C_2") (pintype "bidirectional"))
      (node (ref "LED5") (pin "2") (pinfunction "C_2") (pintype "bidirectional"))
      (node (ref "R13") (pin "P$1") (pinfunction "1_P$1") (pintype "passive"))
      (node (ref "R14") (pin "P$1") (pinfunction "1_P$1") (pintype "passive"))
      (node (ref "R16") (pin "P$1") (pinfunction "1_P$1") (pintype "passive"))
      (node (ref "R20") (pin "P$1") (pinfunction "1_P$1") (pintype "passive"))
      (node (ref "R21") (pin "P$1") (pinfunction "1_P$1") (pintype "passive"))
      (node (ref "R22") (pin "1") (pinfunction "1_1") (pintype "passive"))
      (node (ref "R37") (pin "P$1") (pinfunction "1_P$1") (pintype "passive"))
      (node (ref "R38") (pin "P$1") (pinfunction "1_P$1") (pintype "passive"))
      (node (ref "R4") (pin "P$1") (pinfunction "1_P$1") (pintype "passive"))
      (node (ref "R7") (pin "1") (pinfunction "1_1") (pintype "passive"))
      (node (ref "R78") (pin "2") (pinfunction "2_2") (pintype "passive"))
      (node (ref "R79") (pin "2") (pinfunction "2_2") (pintype "passive"))
      (node (ref "R8") (pin "1") (pinfunction "1_1") (pintype "passive"))
      (node (ref "R80") (pin "2") (pinfunction "2_2") (pintype "passive"))
      (node (ref "R81") (pin "2") (pinfunction "2_2") (pintype "passive"))
      (node (ref "SW1") (pin "3") (pinfunction "2_3") (pintype "bidirectional"))
      (node (ref "SW1") (pin "4") (pinfunction "4_4") (pintype "bidirectional"))
      (node (ref "SW1") (pin "K") (pinfunction "C_K") (pintype "passive"))
      (node (ref "SW2") (pin "3") (pinfunction "2_3") (pintype "bidirectional"))
      (node (ref "SW2") (pin "4") (pinfunction "4_4") (pintype "bidirectional"))
      (node (ref "SW2") (pin "K") (pinfunction "C_K") (pintype "passive"))
      (node (ref "SW3") (pin "1") (pinfunction "1_1") (pintype "passive"))
      (node (ref "SW3") (pin "2") (pinfunction "2_2") (pintype "passive"))
      (node (ref "SW4") (pin "1") (pinfunction "1_1") (pintype "passive"))
      (node (ref "SW4") (pin "2") (pinfunction "2_2") (pintype "passive"))
      (node (ref "SW5") (pin "1") (pinfunction "1_1") (pintype "passive"))
      (node (ref "SW5") (pin "2") (pinfunction "2_2") (pintype "passive"))
      (node (ref "SW6") (pin "1") (pinfunction "1_1") (pintype "passive"))
      (node (ref "SW6") (pin "2") (pinfunction "2_2") (pintype "passive"))
      (node (ref "SW7") (pin "1") (pinfunction "1_1") (pintype "passive"))
      (node (ref "SW7") (pin "2") (pinfunction "2_2") (pintype "passive"))
    )
    (net (code "4") (name "NORMALIZATION_PROBE") (class "Default")
      (node (ref "D3") (pin "3") (pinfunction "AC_3") (pintype "passive"))
      (node (ref "JP39") (pin "1") (pinfunction "1_1") (pintype "passive"))
      (node (ref "R76") (pin "1") (pinfunction "1_1") (pintype "passive"))
      (node (ref "R77") (pin "1") (pinfunction "1_1") (pintype "passive"))
    )
    (net (code "5") (name "Net-(IC10A-+IN)") (class "Default")
      (node (ref "IC10") (pin "3") (pinfunction "+IN_3") (pintype "input"))
      (node (ref "JP48") (pin "1") (pinfunction "1_1") (pintype "passive"))
    )
    (net (code "6") (name "Net-(IC10A--IN)") (class "Default")
      (node (ref "IC10") (pin "2") (pinfunction "-IN_2") (pintype "input"))
      (node (ref "LED10") (pin "2") (pinfunction "2_2") (pintype "bidirectional"))
      (node (ref "R79") (pin "1") (pinfunction "1_1") (pintype "passive"))
    )
    (net (code "7") (name "Net-(IC10A-OUT)") (class "Default")
      (node (ref "IC10") (pin "1") (pinfunction "OUT_1") (pintype "output"))
      (node (ref "LED10") (pin "1") (pinfunction "1_1") (pintype "bidirectional"))
    )
    (net (code "8") (name "Net-(IC10B-+IN)") (class "Default")
      (node (ref "IC10") (pin "5") (pinfunction "+IN_5") (pintype "input"))
      (node (ref "JP53") (pin "1") (pinfunction "1_1") (pintype "passive"))
    )
    (net (code "9") (name "Net-(IC10B--IN)") (class "Default")
      (node (ref "IC10") (pin "6") (pinfunction "-IN_6") (pintype "input"))
      (node (ref "LED9") (pin "2") (pinfunction "2_2") (pintype "bidirectional"))
      (node (ref "R78") (pin "1") (pinfunction "1_1") (pintype "passive"))
    )
    (net (code "10") (name "Net-(IC10B-OUT)") (class "Default")
      (node (ref "IC10") (pin "7") (pinfunction "OUT_7") (pintype "output"))
      (node (ref "LED9") (pin "1") (pinfunction "1_1") (pintype "bidirectional"))
    )
    (net (code "11") (name "Net-(IC10C-+IN)") (class "Default")
      (node (ref "IC10") (pin "10") (pinfunction "+IN_10") (pintype "input"))
      (node (ref "JP50") (pin "1") (pinfunction "1_1") (pintype "passive"))
    )
    (net (code "12") (name "Net-(IC10C--IN)") (class "Default")
      (node (ref "IC10") (pin "9") (pinfunction "-IN_9") (pintype "input"))
      (node (ref "LED12") (pin "2") (pinfunction "2_2") (pintype "bidirectional"))
      (node (ref "R81") (pin "1") (pinfunction "1_1") (pintype "passive"))
    )
    (net (code "13") (name "Net-(IC10C-OUT)") (class "Default")
      (node (ref "IC10") (pin "8") (pinfunction "OUT_8") (pintype "output"))
      (node (ref "LED12") (pin "1") (pinfunction "1_1") (pintype "bidirectional"))
    )
    (net (code "14") (name "Net-(IC10D-+IN)") (class "Default")
      (node (ref "IC10") (pin "12") (pinfunction "+IN_12") (pintype "input"))
      (node (ref "JP46") (pin "1") (pinfunction "1_1") (pintype "passive"))
    )
    (net (code "15") (name "Net-(IC10D--IN)") (class "Default")
      (node (ref "IC10") (pin "13") (pinfunction "-IN_13") (pintype "input"))
      (node (ref "LED11") (pin "2") (pinfunction "2_2") (pintype "bidirectional"))
      (node (ref "R80") (pin "1") (pinfunction "1_1") (pintype "passive"))
    )
    (net (code "16") (name "Net-(IC10D-OUT)") (class "Default")
      (node (ref "IC10") (pin "14") (pinfunction "OUT_14") (pintype "output"))
      (node (ref "LED11") (pin "1") (pinfunction "1_1") (pintype "bidirectional"))
    )
    (net (code "17") (name "Net-(IC10E-V+)") (class "Default")
      (node (ref "C48") (pin "1") (pinfunction "1_1") (pintype "passive"))
      (node (ref "IC10") (pin "4") (pinfunction "V+_4") (pintype "power_in"))
      (node (ref "JP54") (pin "1") (pinfunction "1_1") (pintype "passive"))
    )
    (net (code "18") (name "Net-(IC10E-V-)") (class "Default")
      (node (ref "C49") (pin "2") (pinfunction "2_2") (pintype "passive"))
      (node (ref "IC10") (pin "11") (pinfunction "V-_11") (pintype "power_in"))
      (node (ref "JP55") (pin "1") (pinfunction "1_1") (pintype "passive"))
    )
    (net (code "19") (name "Net-(J1-3)") (class "Default")
      (node (ref "C53") (pin "1") (pinfunction "1_1") (pintype "passive"))
      (node (ref "J1") (pin "P3") (pinfunction "3_P3") (pintype "passive"))
      (node (ref "JP2") (pin "1") (pinfunction "1_1") (pintype "passive"))
    )
    (net (code "20") (name "Net-(J2-3)") (class "Default")
      (node (ref "C45") (pin "1") (pinfunction "1_1") (pintype "passive"))
      (node (ref "J2") (pin "P3") (pinfunction "3_P3") (pintype "passive"))
      (node (ref "JP36") (pin "1") (pinfunction "1_1") (pintype "passive"))
    )
    (net (code "21") (name "Net-(J3-2)") (class "Default")
      (node (ref "J3") (pin "P2") (pinfunction "2_P2") (pintype "passive"))
      (node (ref "R76") (pin "2") (pinfunction "2_2") (pintype "passive"))
    )
    (net (code "22") (name "Net-(J3-3)") (class "Default")
      (node (ref "J3") (pin "P3") (pinfunction "3_P3") (pintype "passive"))
      (node (ref "R26") (pin "1") (pinfunction "1_1") (pintype "passive"))
    )
    (net (code "23") (name "Net-(J4-3)") (class "Default")
      (node (ref "C56") (pin "1") (pinfunction "1_1") (pintype "passive"))
      (node (ref "J4") (pin "P3") (pinfunction "3_P3") (pintype "passive"))
      (node (ref "JP32") (pin "1") (pinfunction "1_1") (pintype "passive"))
    )
    (net (code "24") (name "Net-(J5-3)") (class "Default")
      (node (ref "C58") (pin "1") (pinfunction "1_1") (pintype "passive"))
      (node (ref "J5") (pin "P3") (pinfunction "3_P3") (pintype "passive"))
      (node (ref "JP35") (pin "1") (pinfunction "1_1") (pintype "passive"))
    )
    (net (code "25") (name "Net-(J6-3)") (class "Default")
      (node (ref "C54") (pin "1") (pinfunction "1_1") (pintype "passive"))
      (node (ref "J6") (pin "P3") (pinfunction "3_P3") (pintype "passive"))
      (node (ref "JP34") (pin "1") (pinfunction "1_1") (pintype "passive"))
    )
    (net (code "26") (name "Net-(J7-3)") (class "Default")
      (node (ref "C55") (pin "1") (pinfunction "1_1") (pintype "passive"))
      (node (ref "J7") (pin "P3") (pinfunction "3_P3") (pintype "passive"))
      (node (ref "JP4") (pin "1") (pinfunction "1_1") (pintype "passive"))
    )
    (net (code "27") (name "Net-(J8-3)") (class "Default")
      (node (ref "C57") (pin "1") (pinfunction "1_1") (pintype "passive"))
      (node (ref "J8") (pin "P3") (pinfunction "3_P3") (pintype "passive"))
      (node (ref "JP33") (pin "1") (pinfunction "1_1") (pintype "passive"))
    )
    (net (code "28") (name "Net-(J9-2)") (class "Default")
      (node (ref "J9") (pin "P2") (pinfunction "2_P2") (pintype "passive"))
      (node (ref "R77") (pin "2") (pinfunction "2_2") (pintype "passive"))
    )
    (net (code "29") (name "Net-(J9-3)") (class "Default")
      (node (ref "J9") (pin "P3") (pinfunction "3_P3") (pintype "passive"))
      (node (ref "R27") (pin "1") (pinfunction "1_1") (pintype "passive"))
    )
    (net (code "30") (name "Net-(J10-3)") (class "Default")
      (node (ref "J10") (pin "P3") (pinfunction "3_P3") (pintype "passive"))
      (node (ref "JP41") (pin "1") (pinfunction "1_1") (pintype "passive"))
    )
    (net (code "31") (name "Net-(J11-3)") (class "Default")
      (node (ref "J11") (pin "P3") (pinfunction "3_P3") (pintype "passive"))
      (node (ref "JP43") (pin "1") (pinfunction "1_1") (pintype "passive"))
    )
    (net (code "32") (name "Net-(J12-3)") (class "Default")
      (node (ref "J12") (pin "P3") (pinfunction "3_P3") (pintype "passive"))
      (node (ref "JP45") (pin "1") (pinfunction "1_1") (pintype "passive"))
    )
    (net (code "33") (name "Net-(J13-3)") (class "Default")
      (node (ref "J13") (pin "P3") (pinfunction "3_P3") (pintype "passive"))
      (node (ref "JP47") (pin "1") (pinfunction "1_1") (pintype "passive"))
    )
    (net (code "34") (name "Net-(J14-3)") (class "Default")
      (node (ref "J14") (pin "P3") (pinfunction "3_P3") (pintype "passive"))
      (node (ref "JP56") (pin "1") (pinfunction "1_1") (pintype "passive"))
    )
    (net (code "35") (name "Net-(J15-3)") (class "Default")
      (node (ref "J15") (pin "P3") (pinfunction "3_P3") (pintype "passive"))
      (node (ref "JP49") (pin "1") (pinfunction "1_1") (pintype "passive"))
    )
    (net (code "36") (name "Net-(J16-3)") (class "Default")
      (node (ref "J16") (pin "P3") (pinfunction "3_P3") (pintype "passive"))
      (node (ref "JP51") (pin "1") (pinfunction "1_1") (pintype "passive"))
    )
    (net (code "37") (name "Net-(JP14-Pad1)") (class "Default")
      (node (ref "JP14") (pin "1") (pinfunction "1_1") (pintype "passive"))
      (node (ref "R1") (pin "1") (pinfunction "1_1") (pintype "passive"))
    )
    (net (code "38") (name "Net-(JP16-Pad1)") (class "Default")
      (node (ref "JP16") (pin "1") (pinfunction "1_1") (pintype "passive"))
      (node (ref "R5") (pin "1") (pinfunction "1_1") (pintype "passive"))
    )
    (net (code "39") (name "Net-(JP18-Pad1)") (class "Default")
      (node (ref "JP18") (pin "1") (pinfunction "1_1") (pintype "passive"))
      (node (ref "SW7") (pin "3") (pinfunction "3_3") (pintype "passive"))
      (node (ref "SW7") (pin "4") (pinfunction "4_4") (pintype "passive"))
    )
    (net (code "40") (name "Net-(JP19-Pad1)") (class "Default")
      (node (ref "JP19") (pin "1") (pinfunction "1_1") (pintype "passive"))
      (node (ref "SW5") (pin "3") (pinfunction "3_3") (pintype "passive"))
      (node (ref "SW5") (pin "4") (pinfunction "4_4") (pintype "passive"))
    )
    (net (code "41") (name "Net-(JP20-Pad1)") (class "Default")
      (node (ref "JP20") (pin "1") (pinfunction "1_1") (pintype "passive"))
      (node (ref "SW3") (pin "3") (pinfunction "3_3") (pintype "passive"))
      (node (ref "SW3") (pin "4") (pinfunction "4_4") (pintype "passive"))
    )
    (net (code "42") (name "Net-(JP21-Pad1)") (class "Default")
      (node (ref "JP21") (pin "1") (pinfunction "1_1") (pintype "passive"))
      (node (ref "SW4") (pin "3") (pinfunction "3_3") (pintype "passive"))
      (node (ref "SW4") (pin "4") (pinfunction "4_4") (pintype "passive"))
    )
    (net (code "43") (name "Net-(JP22-Pad1)") (class "Default")
      (node (ref "JP22") (pin "1") (pinfunction "1_1") (pintype "passive"))
      (node (ref "SW6") (pin "3") (pinfunction "3_3") (pintype "passive"))
      (node (ref "SW6") (pin "4") (pinfunction "4_4") (pintype "passive"))
    )
    (net (code "44") (name "Net-(JP23-Pad1)") (class "Default")
      (node (ref "JP23") (pin "1") (pinfunction "1_1") (pintype "passive"))
      (node (ref "R36") (pin "1") (pinfunction "1_1") (pintype "passive"))
    )
    (net (code "45") (name "Net-(JP24-Pad1)") (class "Default")
      (node (ref "JP24") (pin "1") (pinfunction "1_1") (pintype "passive"))
      (node (ref "R19") (pin "1") (pinfunction "1_1") (pintype "passive"))
    )
    (net (code "46") (name "Net-(JP25-Pad1)") (class "Default")
      (node (ref "JP25") (pin "1") (pinfunction "1_1") (pintype "passive"))
      (node (ref "R18") (pin "1") (pinfunction "1_1") (pintype "passive"))
    )
    (net (code "47") (name "Net-(JP26-Pad1)") (class "Default")
      (node (ref "JP26") (pin "1") (pinfunction "1_1") (pintype "passive"))
      (node (ref "R9") (pin "1") (pinfunction "1_1") (pintype "passive"))
    )
    (net (code "48") (name "Net-(JP27-Pad1)") (class "Default")
      (node (ref "JP27") (pin "1") (pinfunction "1_1") (pintype "passive"))
      (node (ref "R10") (pin "1") (pinfunction "1_1") (pintype "passive"))
    )
    (net (code "49") (name "Net-(JP28-Pad1)") (class "Default")
      (node (ref "JP28") (pin "1") (pinfunction "1_1") (pintype "passive"))
      (node (ref "R11") (pin "1") (pinfunction "1_1") (pintype "passive"))
    )
    (net (code "50") (name "Net-(JP29-Pad1)") (class "Default")
      (node (ref "JP29") (pin "1") (pinfunction "1_1") (pintype "passive"))
      (node (ref "R12") (pin "1") (pinfunction "1_1") (pintype "passive"))
    )
    (net (code "51") (name "Net-(JP30-Pad1)") (class "Default")
      (node (ref "JP30") (pin "1") (pinfunction "1_1") (pintype "passive"))
      (node (ref "R15") (pin "1") (pinfunction "1_1") (pintype "passive"))
    )
    (net (code "52") (name "Net-(JP31-Pad1)") (class "Default")
      (node (ref "JP31") (pin "1") (pinfunction "1_1") (pintype "passive"))
      (node (ref "R17") (pin "1") (pinfunction "1_1") (pintype "passive"))
    )
    (net (code "53") (name "Net-(JP37-Pad1)") (class "Default")
      (node (ref "JP37") (pin "1") (pinfunction "1_1") (pintype "passive"))
      (node (ref "R26") (pin "2") (pinfunction "2_2") (pintype "passive"))
    )
    (net (code "54") (name "Net-(JP38-Pad1)") (class "Default")
      (node (ref "JP38") (pin "1") (pinfunction "1_1") (pintype "passive"))
      (node (ref "R27") (pin "2") (pinfunction "2_2") (pintype "passive"))
    )
    (net (code "55") (name "Net-(JP40-Pad1)") (class "Default")
      (node (ref "JP40") (pin "1") (pinfunction "1_1") (pintype "passive"))
      (node (ref "LED13") (pin "1") (pinfunction "1_1") (pintype "bidirectional"))
    )
    (net (code "56") (name "Net-(JP42-Pad1)") (class "Default")
      (node (ref "JP42") (pin "1") (pinfunction "1_1") (pintype "passive"))
      (node (ref "LED6") (pin "1") (pinfunction "1_1") (pintype "bidirectional"))
    )
    (net (code "57") (name "Net-(JP44-Pad1)") (class "Default")
      (node (ref "JP44") (pin "1") (pinfunction "1_1") (pintype "passive"))
      (node (ref "LED7") (pin "1") (pinfunction "1_1") (pintype "bidirectional"))
    )
    (net (code "58") (name "Net-(LED1-GRN)") (class "Default")
      (node (ref "LED1") (pin "1") (pinfunction "GRN_1") (pintype "bidirectional"))
      (node (ref "R10") (pin "2") (pinfunction "2_2") (pintype "passive"))
    )
    (net (code "59") (name "Net-(LED1-RED)") (class "Default")
      (node (ref "LED1") (pin "3") (pinfunction "RED_3") (pintype "bidirectional"))
      (node (ref "R9") (pin "2") (pinfunction "2_2") (pintype "passive"))
    )
    (net (code "60") (name "Net-(LED2-GRN)") (class "Default")
      (node (ref "LED2") (pin "1") (pinfunction "GRN_1") (pintype "bidirectional"))
      (node (ref "R12") (pin "2") (pinfunction "2_2") (pintype "passive"))
    )
    (net (code "61") (name "Net-(LED2-RED)") (class "Default")
      (node (ref "LED2") (pin "3") (pinfunction "RED_3") (pintype "bidirectional"))
      (node (ref "R11") (pin "2") (pinfunction "2_2") (pintype "passive"))
    )
    (net (code "62") (name "Net-(LED3-GRN)") (class "Default")
      (node (ref "LED3") (pin "1") (pinfunction "GRN_1") (pintype "bidirectional"))
      (node (ref "R18") (pin "2") (pinfunction "2_2") (pintype "passive"))
    )
    (net (code "63") (name "Net-(LED3-RED)") (class "Default")
      (node (ref "LED3") (pin "3") (pinfunction "RED_3") (pintype "bidirectional"))
      (node (ref "R19") (pin "2") (pinfunction "2_2") (pintype "passive"))
    )
    (net (code "64") (name "Net-(LED4-GRN)") (class "Default")
      (node (ref "LED4") (pin "1") (pinfunction "GRN_1") (pintype "bidirectional"))
      (node (ref "R17") (pin "2") (pinfunction "2_2") (pintype "passive"))
    )
    (net (code "65") (name "Net-(LED4-RED)") (class "Default")
      (node (ref "LED4") (pin "3") (pinfunction "RED_3") (pintype "bidirectional"))
      (node (ref "R15") (pin "2") (pinfunction "2_2") (pintype "passive"))
    )
    (net (code "66") (name "Net-(LED5-GRN)") (class "Default")
      (node (ref "LED5") (pin "1") (pinfunction "GRN_1") (pintype "bidirectional"))
      (node (ref "R36") (pin "2") (pinfunction "2_2") (pintype "passive"))
    )
    (net (code "67") (name "Net-(LED6-Pad2)") (class "Default")
      (node (ref "LED6") (pin "2") (pinfunction "2_2") (pintype "bidirectional"))
      (node (ref "R8") (pin "2") (pinfunction "2_2") (pintype "passive"))
    )
    (net (code "68") (name "Net-(LED7-Pad2)") (class "Default")
      (node (ref "LED7") (pin "2") (pinfunction "2_2") (pintype "bidirectional"))
      (node (ref "R22") (pin "2") (pinfunction "2_2") (pintype "passive"))
    )
    (net (code "69") (name "Net-(LED13-Pad2)") (class "Default")
      (node (ref "LED13") (pin "2") (pinfunction "2_2") (pintype "bidirectional"))
      (node (ref "R7") (pin "2") (pinfunction "2_2") (pintype "passive"))
    )
    (net (code "70") (name "Net-(R1-Pad2)") (class "Default")
      (node (ref "R1") (pin "2") (pinfunction "2_2") (pintype "passive"))
      (node (ref "SW1") (pin "A") (pinfunction "A_A") (pintype "passive"))
    )
    (net (code "71") (name "Net-(R4-2)") (class "Default")
      (node (ref "C8") (pin "1") (pinfunction "1_1") (pintype "passive"))
      (node (ref "JP8") (pin "1") (pinfunction "1_1") (pintype "passive"))
      (node (ref "R4") (pin "P$2") (pinfunction "2_P$2") (pintype "passive"))
    )
    (net (code "72") (name "Net-(R5-Pad2)") (class "Default")
      (node (ref "R5") (pin "2") (pinfunction "2_2") (pintype "passive"))
      (node (ref "SW2") (pin "A") (pinfunction "A_A") (pintype "passive"))
    )
    (net (code "73") (name "Net-(R13-2)") (class "Default")
      (node (ref "C17") (pin "1") (pinfunction "1_1") (pintype "passive"))
      (node (ref "JP7") (pin "1") (pinfunction "1_1") (pintype "passive"))
      (node (ref "R13") (pin "P$2") (pinfunction "2_P$2") (pintype "passive"))
    )
    (net (code "74") (name "Net-(R14-2)") (class "Default")
      (node (ref "C18") (pin "1") (pinfunction "1_1") (pintype "passive"))
      (node (ref "JP12") (pin "1") (pinfunction "1_1") (pintype "passive"))
      (node (ref "R14") (pin "P$2") (pinfunction "2_P$2") (pintype "passive"))
    )
    (net (code "75") (name "Net-(R16-2)") (class "Default")
      (node (ref "C24") (pin "1") (pinfunction "1_1") (pintype "passive"))
      (node (ref "JP9") (pin "1") (pinfunction "1_1") (pintype "passive"))
      (node (ref "R16") (pin "P$2") (pinfunction "2_P$2") (pintype "passive"))
    )
    (net (code "76") (name "Net-(R20-2)") (class "Default")
      (node (ref "C28") (pin "1") (pinfunction "1_1") (pintype "passive"))
      (node (ref "JP5") (pin "1") (pinfunction "1_1") (pintype "passive"))
      (node (ref "R20") (pin "P$2") (pinfunction "2_P$2") (pintype "passive"))
    )
    (net (code "77") (name "Net-(R21-2)") (class "Default")
      (node (ref "C29") (pin "1") (pinfunction "1_1") (pintype "passive"))
      (node (ref "JP13") (pin "1") (pinfunction "1_1") (pintype "passive"))
      (node (ref "R21") (pin "P$2") (pinfunction "2_P$2") (pintype "passive"))
    )
    (net (code "78") (name "Net-(R37-2)") (class "Default")
      (node (ref "C38") (pin "1") (pinfunction "1_1") (pintype "passive"))
      (node (ref "JP10") (pin "1") (pinfunction "1_1") (pintype "passive"))
      (node (ref "R37") (pin "P$2") (pinfunction "2_P$2") (pintype "passive"))
    )
    (net (code "79") (name "Net-(R38-2)") (class "Default")
      (node (ref "C36") (pin "1") (pinfunction "1_1") (pintype "passive"))
      (node (ref "JP11") (pin "1") (pinfunction "1_1") (pintype "passive"))
      (node (ref "R38") (pin "P$2") (pinfunction "2_P$2") (pintype "passive"))
    )
    (net (code "80") (name "Net-(SW1A-1)") (class "Default")
      (node (ref "JP15") (pin "1") (pinfunction "1_1") (pintype "passive"))
      (node (ref "SW1") (pin "1") (pinfunction "3_1") (pintype "bidirectional"))
      (node (ref "SW1") (pin "2") (pinfunction "1_2") (pintype "bidirectional"))
    )
    (net (code "81") (name "Net-(SW2A-1)") (class "Default")
      (node (ref "JP17") (pin "1") (pinfunction "1_1") (pintype "passive"))
      (node (ref "SW2") (pin "1") (pinfunction "3_1") (pintype "bidirectional"))
      (node (ref "SW2") (pin "2") (pinfunction "1_2") (pintype "bidirectional"))
    )
    (net (code "82") (name "unconnected-(J10-2-PadP2)") (class "Default")
      (node (ref "J10") (pin "P2") (pinfunction "2_P2") (pintype "passive"))
    )
    (net (code "83") (name "unconnected-(J11-2-PadP2)") (class "Default")
      (node (ref "J11") (pin "P2") (pinfunction "2_P2") (pintype "passive"))
    )
    (net (code "84") (name "unconnected-(J12-2-PadP2)") (class "Default")
      (node (ref "J12") (pin "P2") (pinfunction "2_P2") (pintype "passive"))
    )
    (net (code "85") (name "unconnected-(J13-2-PadP2)") (class "Default")
      (node (ref "J13") (pin "P2") (pinfunction "2_P2") (pintype "passive"))
    )
    (net (code "86") (name "unconnected-(J14-2-PadP2)") (class "Default")
      (node (ref "J14") (pin "P2") (pinfunction "2_P2") (pintype "passive"))
    )
    (net (code "87") (name "unconnected-(J15-2-PadP2)") (class "Default")
      (node (ref "J15") (pin "P2") (pinfunction "2_P2") (pintype "passive"))
    )
    (net (code "88") (name "unconnected-(J16-2-PadP2)") (class "Default")
      (node (ref "J16") (pin "P2") (pinfunction "2_P2") (pintype "passive"))
    )
    (net (code "89") (name "unconnected-(LED5-RED-Pad3)") (class "Default")
      (node (ref "LED5") (pin "3") (pinfunction "RED_3") (pintype "bidirectional"))
    )
  )
)
